# Universal_USB-UART_Adapter.net
KiCad netlist of a schematic drawn in EAGLE
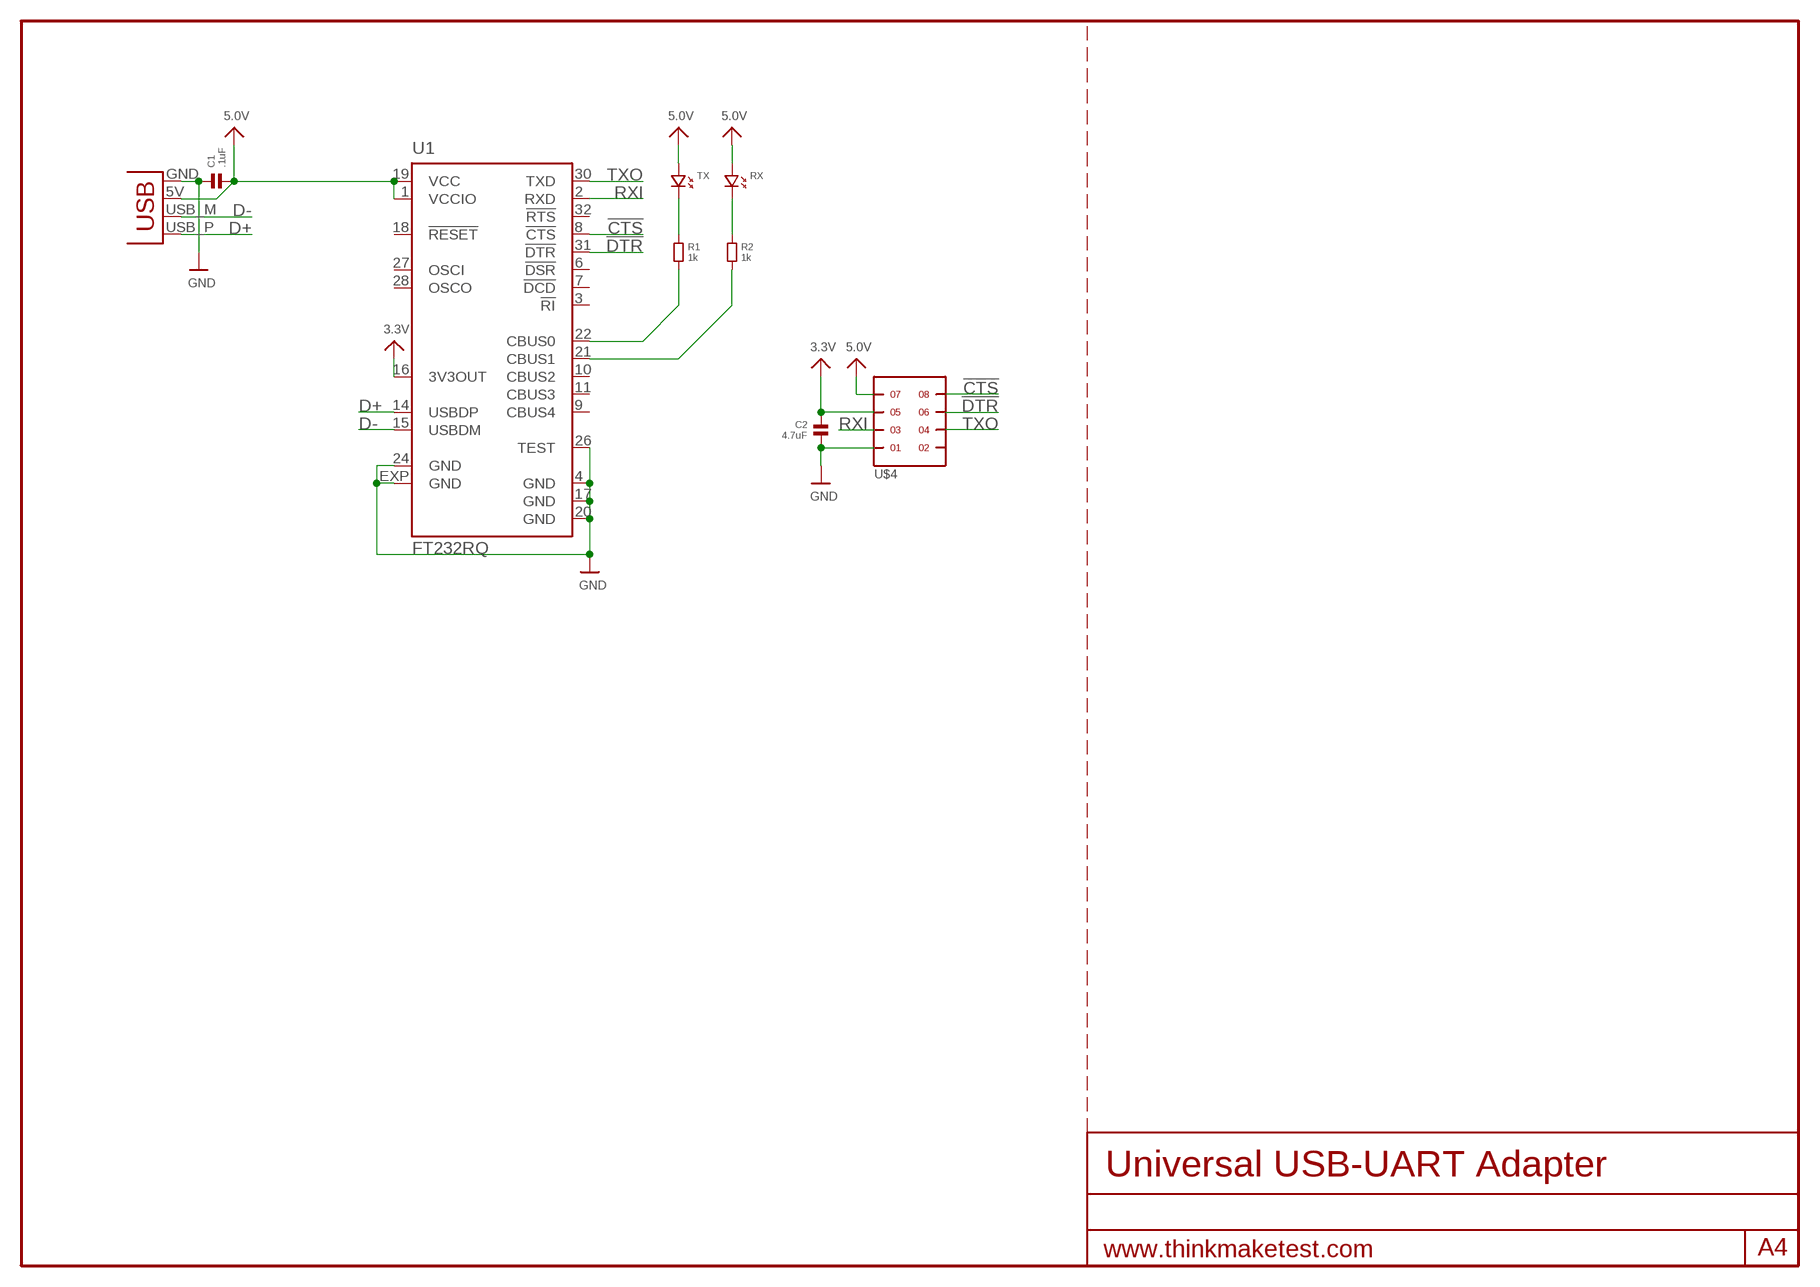
[diagram p0: schematic, sheet 1]

(export (version "E")
  (design (tool "Eeschema 10.0.6"))
  (components
    (comp (ref "C1")
      (value ".1uF")
      (footprint "eagle-import:0603")
      (libsource (lib "eagle-import") (part "CAPACITOR.0603"))
    )
    (comp (ref "C2")
      (value "4.7uF")
      (footprint "eagle-import:0603")
      (libsource (lib "eagle-import") (part "CAPACITOR.0603"))
    )
    (comp (ref "R1")
      (value "1k")
      (footprint "eagle-import:0603")
      (libsource (lib "eagle-import") (part "RESISTOR.0603"))
    )
    (comp (ref "R2")
      (value "1k")
      (footprint "eagle-import:0603")
      (libsource (lib "eagle-import") (part "RESISTOR.0603"))
    )
    (comp (ref "RX")
      (value "LED.0603")
      (footprint "eagle-import:0603.LED")
      (libsource (lib "eagle-import") (part "LED.0603"))
    )
    (comp (ref "TX")
      (value "LED.0603")
      (footprint "eagle-import:0603.LED")
      (libsource (lib "eagle-import") (part "LED.0603"))
    )
    (comp (ref "U$4")
      (value "MMT-104-01-X-DH-X")
      (footprint "eagle-import:MMT-104-01-X-DH-X")
      (libsource (lib "eagle-import") (part "MMT-104-01-X-DH-X"))
    )
    (comp (ref "U1")
      (value "FT232RQ")
      (footprint "eagle-import:QFN32")
      (libsource (lib "eagle-import") (part "FT232RQ"))
    )
    (comp (ref "X1")
      (value "USBPCB")
      (footprint "eagle-import:USB-A-PCB")
      (libsource (lib "eagle-import") (part "USBPCB"))
    )
  )
  (nets
    (net (code "1") (name "/D+") (class "Default")
      (node (ref "U1") (pin "14") (pinfunction "USBDP_14") (pintype "bidirectional"))
      (node (ref "X1") (pin "USB_P") (pinfunction "D+_USB_P") (pintype "bidirectional"))
    )
    (net (code "2") (name "/D-") (class "Default")
      (node (ref "U1") (pin "15") (pinfunction "USBDM_15") (pintype "bidirectional"))
      (node (ref "X1") (pin "USB_M") (pinfunction "D-_USB_M") (pintype "bidirectional"))
    )
    (net (code "3") (name "/RXI") (class "Default")
      (node (ref "U$4") (pin "3") (pinfunction "3_3") (pintype "bidirectional"))
      (node (ref "U1") (pin "2") (pinfunction "RXD_2") (pintype "input"))
    )
    (net (code "4") (name "/TXO") (class "Default")
      (node (ref "U$4") (pin "4") (pinfunction "4_4") (pintype "bidirectional"))
      (node (ref "U1") (pin "30") (pinfunction "TXD_30") (pintype "output"))
    )
    (net (code "5") (name "/~{CTS}") (class "Default")
      (node (ref "U$4") (pin "8") (pinfunction "8_8") (pintype "bidirectional"))
      (node (ref "U1") (pin "8") (pinfunction "~{CTS}_8") (pintype "input"))
    )
    (net (code "6") (name "/~{DTR}") (class "Default")
      (node (ref "U$4") (pin "6") (pinfunction "6_6") (pintype "bidirectional"))
      (node (ref "U1") (pin "31") (pinfunction "~{DTR}_31") (pintype "output"))
    )
    (net (code "7") (name "3.3V") (class "Default")
      (node (ref "C2") (pin "1") (pinfunction "1_1") (pintype "bidirectional"))
      (node (ref "U$4") (pin "5") (pinfunction "5_5") (pintype "bidirectional"))
      (node (ref "U1") (pin "16") (pinfunction "3V3OUT_16") (pintype "output"))
    )
    (net (code "8") (name "5.0V") (class "Default")
      (node (ref "C1") (pin "2") (pinfunction "2_2") (pintype "bidirectional"))
      (node (ref "RX") (pin "P$1") (pinfunction "1_P$1") (pintype "bidirectional"))
      (node (ref "TX") (pin "P$1") (pinfunction "1_P$1") (pintype "bidirectional"))
      (node (ref "U$4") (pin "7") (pinfunction "7_7") (pintype "bidirectional"))
      (node (ref "U1") (pin "1") (pinfunction "VCCIO_1") (pintype "power_in"))
      (node (ref "U1") (pin "19") (pinfunction "VCC_19") (pintype "power_in"))
      (node (ref "X1") (pin "5V") (pinfunction "VBUS_5V") (pintype "bidirectional"))
    )
    (net (code "9") (name "GND") (class "Default")
      (node (ref "C1") (pin "1") (pinfunction "1_1") (pintype "bidirectional"))
      (node (ref "C2") (pin "2") (pinfunction "2_2") (pintype "bidirectional"))
      (node (ref "U$4") (pin "1") (pinfunction "1_1") (pintype "bidirectional"))
      (node (ref "U1") (pin "17") (pinfunction "GND_17") (pintype "power_in"))
      (node (ref "U1") (pin "20") (pinfunction "GND_20") (pintype "power_in"))
      (node (ref "U1") (pin "24") (pinfunction "GND_24") (pintype "power_in"))
      (node (ref "U1") (pin "26") (pinfunction "TEST_26") (pintype "input"))
      (node (ref "U1") (pin "4") (pinfunction "GND_4") (pintype "power_in"))
      (node (ref "U1") (pin "EXP") (pinfunction "GND_EXP") (pintype "power_in"))
      (node (ref "X1") (pin "GND") (pinfunction "GND_GND") (pintype "bidirectional"))
    )
    (net (code "10") (name "Net-(RX-2)") (class "Default")
      (node (ref "R2") (pin "1") (pinfunction "1_1") (pintype "bidirectional"))
      (node (ref "RX") (pin "P$2") (pinfunction "2_P$2") (pintype "bidirectional"))
    )
    (net (code "11") (name "Net-(TX-2)") (class "Default")
      (node (ref "R1") (pin "1") (pinfunction "1_1") (pintype "bidirectional"))
      (node (ref "TX") (pin "P$2") (pinfunction "2_P$2") (pintype "bidirectional"))
    )
    (net (code "12") (name "Net-(U1-CBUS0)") (class "Default")
      (node (ref "R1") (pin "2") (pinfunction "2_2") (pintype "bidirectional"))
      (node (ref "U1") (pin "22") (pinfunction "CBUS0_22") (pintype "bidirectional"))
    )
    (net (code "13") (name "Net-(U1-CBUS1)") (class "Default")
      (node (ref "R2") (pin "2") (pinfunction "2_2") (pintype "bidirectional"))
      (node (ref "U1") (pin "21") (pinfunction "CBUS1_21") (pintype "bidirectional"))
    )
    (net (code "14") (name "unconnected-(U$4-Pad2)") (class "Default")
      (node (ref "U$4") (pin "2") (pinfunction "2_2") (pintype "bidirectional"))
    )
    (net (code "15") (name "unconnected-(U1-CBUS2-Pad10)") (class "Default")
      (node (ref "U1") (pin "10") (pinfunction "CBUS2_10") (pintype "bidirectional"))
    )
    (net (code "16") (name "unconnected-(U1-CBUS3-Pad11)") (class "Default")
      (node (ref "U1") (pin "11") (pinfunction "CBUS3_11") (pintype "bidirectional"))
    )
    (net (code "17") (name "unconnected-(U1-CBUS4-Pad9)") (class "Default")
      (node (ref "U1") (pin "9") (pinfunction "CBUS4_9") (pintype "bidirectional"))
    )
    (net (code "18") (name "unconnected-(U1-OSCI-Pad27)") (class "Default")
      (node (ref "U1") (pin "27") (pinfunction "OSCI_27") (pintype "input"))
    )
    (net (code "19") (name "unconnected-(U1-OSCO-Pad28)") (class "Default")
      (node (ref "U1") (pin "28") (pinfunction "OSCO_28") (pintype "output"))
    )
    (net (code "20") (name "unconnected-(U1-~{DCD}-Pad7)") (class "Default")
      (node (ref "U1") (pin "7") (pinfunction "~{DCD}_7") (pintype "input"))
    )
    (net (code "21") (name "unconnected-(U1-~{DSR}-Pad6)") (class "Default")
      (node (ref "U1") (pin "6") (pinfunction "~{DSR}_6") (pintype "input"))
    )
    (net (code "22") (name "unconnected-(U1-~{RESET}-Pad18)") (class "Default")
      (node (ref "U1") (pin "18") (pinfunction "~{RESET}_18") (pintype "input"))
    )
    (net (code "23") (name "unconnected-(U1-~{RI}-Pad3)") (class "Default")
      (node (ref "U1") (pin "3") (pinfunction "~{RI}_3") (pintype "input"))
    )
    (net (code "24") (name "unconnected-(U1-~{RTS}-Pad32)") (class "Default")
      (node (ref "U1") (pin "32") (pinfunction "~{RTS}_32") (pintype "output"))
    )
  )
)
